# cSLIM-SA_power.net
KiCad netlist of a schematic drawn in Altium Designer
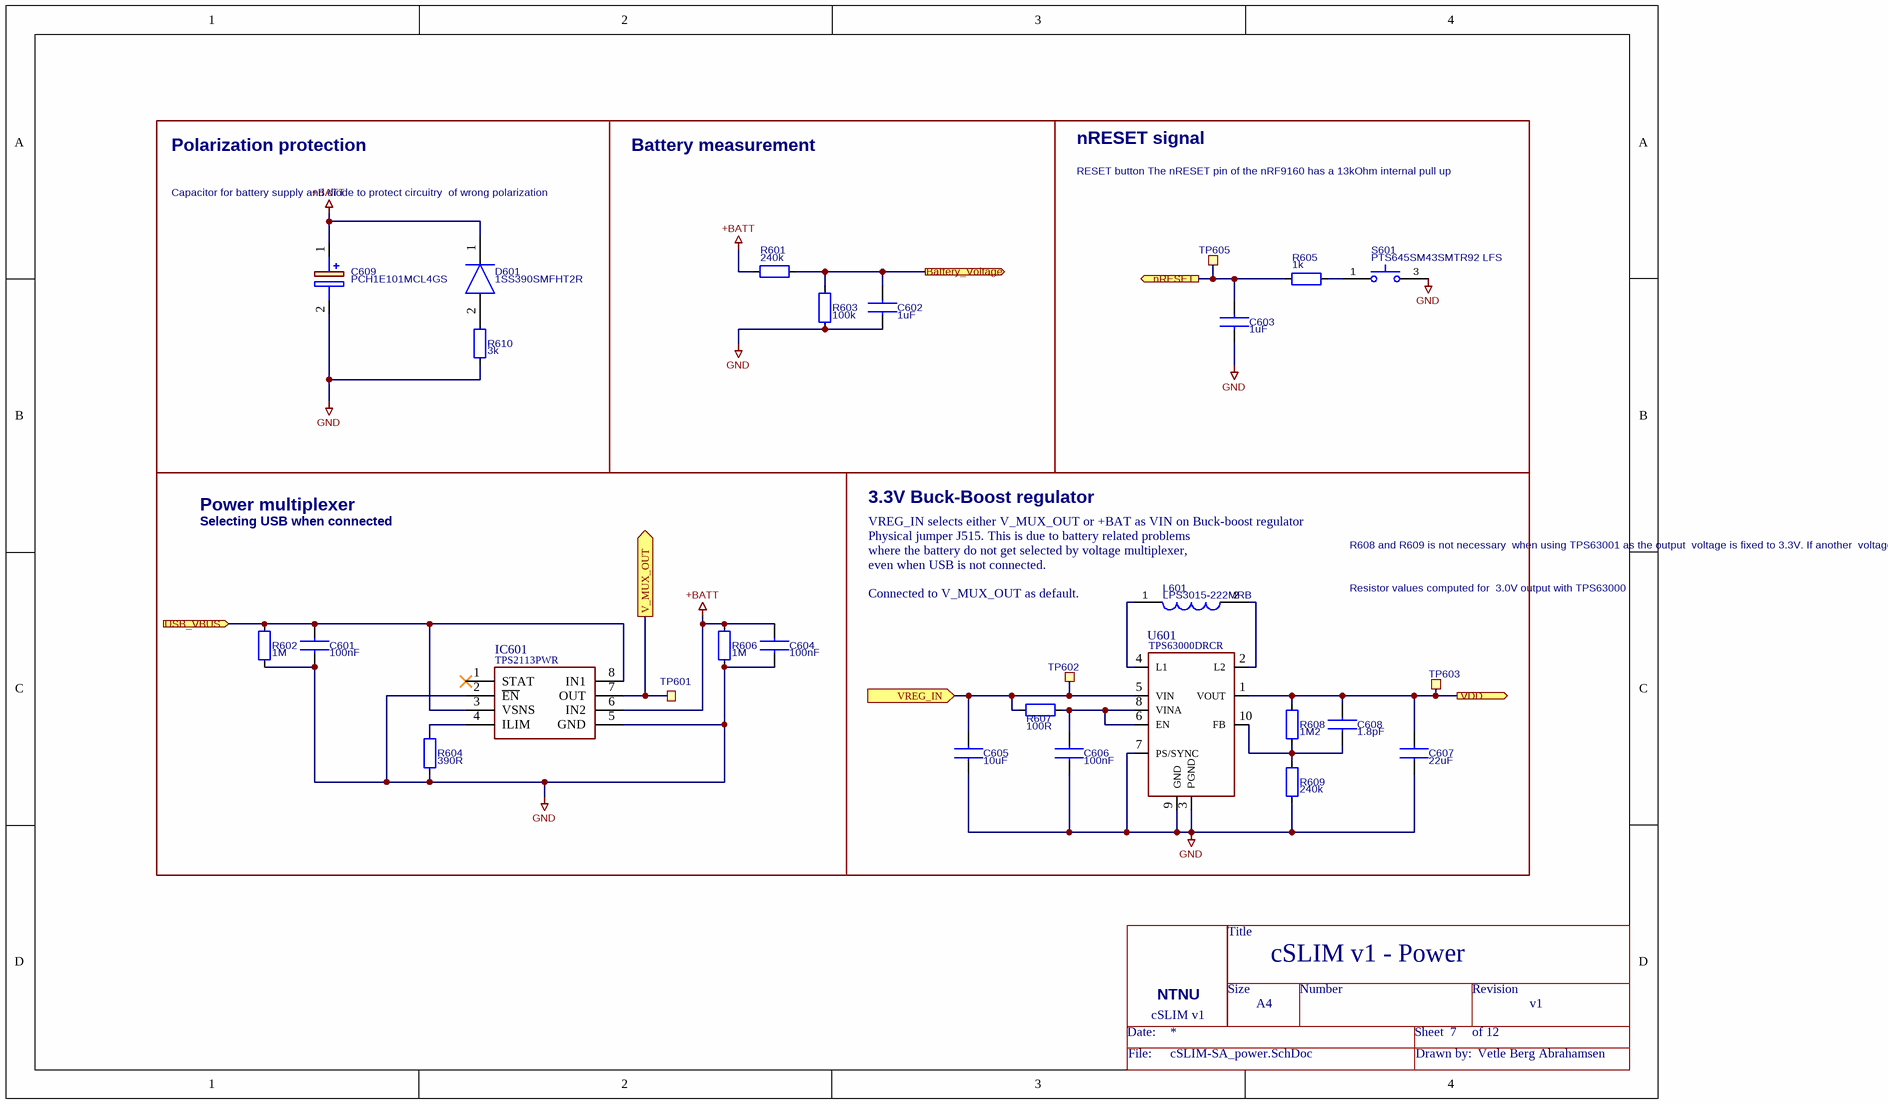
[diagram p0: cSLIM-SA_power.SchDoc]

(export (version "E")
  (design (tool "Eeschema 10.0.6"))
  (components
    (comp (ref "C601")
      (value "100nF")
      (footprint "cSLIM-SA:CAPC1608X90N")
      (description "Capacitor")
      (fields (field (name "MANUFACTURER_PART_NUMBER") "CL10B104KB8NNNL"))
      (libsource (lib "cSLIM-SA") (part "C"))
    )
    (comp (ref "C602")
      (value "1uF")
      (footprint "cSLIM-SA:CAPC1608X90N")
      (description "Capacitor")
      (fields (field (name "MANUFACTURER_PART_NUMBER") "CL10A105KO8NNNC"))
      (libsource (lib "cSLIM-SA") (part "C"))
    )
    (comp (ref "C603")
      (value "1uF")
      (footprint "cSLIM-SA:CAPC1608X90N")
      (description "Capacitor")
      (fields (field (name "MANUFACTURER_PART_NUMBER") "CL10A105KO8NNNC"))
      (libsource (lib "cSLIM-SA") (part "C"))
    )
    (comp (ref "C604")
      (value "100nF")
      (footprint "cSLIM-SA:CAPC1608X90N")
      (description "Capacitor")
      (fields (field (name "MANUFACTURER_PART_NUMBER") "CL10B104KB8NNNL"))
      (libsource (lib "cSLIM-SA") (part "C"))
    )
    (comp (ref "C605")
      (value "10uF")
      (footprint "cSLIM-SA:CAPC1608X90N")
      (description "Capacitor")
      (fields (field (name "MANUFACTURER_PART_NUMBER") "CL10X106MP8NRNC"))
      (libsource (lib "cSLIM-SA") (part "C"))
    )
    (comp (ref "C606")
      (value "100nF")
      (footprint "cSLIM-SA:CAPC1608X90N")
      (description "Capacitor")
      (fields (field (name "MANUFACTURER_PART_NUMBER") "CL10B104KB8NNNL"))
      (libsource (lib "cSLIM-SA") (part "C"))
    )
    (comp (ref "C607")
      (value "22uF")
      (footprint "cSLIM-SA:CAPC1608X90N")
      (description "Capacitor")
      (fields (field (name "MANUFACTURER_PART_NUMBER") "CL10A226KQ8NRNE"))
      (libsource (lib "cSLIM-SA") (part "C"))
    )
    (comp (ref "C608")
      (value "1.8pF")
      (footprint "cSLIM-SA:CAPC1608X90N")
      (description "Capacitor")
      (fields (field (name "MANUFACTURER_PART_NUMBER") "CL10C1R8BB8NNNC"))
      (libsource (lib "cSLIM-SA") (part "C"))
    )
    (comp (ref "C609")
      (value "PCH1E101MCL4GS")
      (footprint "cSLIM-SA:CAPAE660X840N")
      (description "Aluminium Organic Polymer Capacitors 100UF 25V ESR=27")
      (fields (field (name "MOUSER PART NUMBER") "647-PCH1E101MCL4GS"))
      (libsource (lib "cSLIM-SA") (part "PCH1E101MCL4GS"))
    )
    (comp (ref "D601")
      (value "1SS390SMFHT2R")
      (footprint "cSLIM-SA:SODFL1608X70N")
      (description "RF Diode PIN - Single 35V 100 mA EMD2")
      (fields (field (name "MOUSER PART NUMBER") "755-1SS390SMFHT2R"))
      (libsource (lib "cSLIM-SA") (part "1SS390SMFHT2R"))
    )
    (comp (ref "IC601")
      (value "TPS2113PWR")
      (footprint "cSLIM-SA:SOP65P640X120-8N")
      (description "OR Controller Source Selector Switch N-Channel 2:1 8-TSSOP")
      (fields (field (name "MOUSER PART NUMBER") "595-TPS2113PWR"))
      (libsource (lib "cSLIM-SA") (part "TPS2113PWR"))
    )
    (comp (ref "L601")
      (value "LPS3015-222MRB")
      (footprint "cSLIM-SA:LPS3015")
      (libsource (lib "cSLIM-SA") (part "LPS3015-103MRB"))
    )
    (comp (ref "R601")
      (value "240k")
      (footprint "cSLIM-SA:RESC1608X55N")
      (fields (field (name "MANUFACTURER_PART_NUMBER") "RC0603FR-07240KL"))
      (libsource (lib "cSLIM-SA") (part "R"))
    )
    (comp (ref "R602")
      (value "1M")
      (footprint "cSLIM-SA:RESC1608X55N")
      (fields (field (name "MANUFACTURER_PART_NUMBER") "RC0603FR-131ML"))
      (libsource (lib "") (part "R_1"))
    )
    (comp (ref "R603")
      (value "100k")
      (footprint "cSLIM-SA:RESC1608X55N")
      (fields (field (name "MANUFACTURER_PART_NUMBER") "RC0603FR-07100KL"))
      (libsource (lib "") (part "R_1"))
    )
    (comp (ref "R604")
      (value "390R")
      (footprint "cSLIM-SA:RESC1608X55N")
      (fields (field (name "MANUFACTURER_PART_NUMBER") "RC0603JR-07390RL"))
      (libsource (lib "") (part "R_1"))
    )
    (comp (ref "R605")
      (value "1k")
      (footprint "cSLIM-SA:RESC1608X55N")
      (fields (field (name "MANUFACTURER_PART_NUMBER") "RC0603FR-071KL"))
      (libsource (lib "") (part "R_2"))
    )
    (comp (ref "R606")
      (value "1M")
      (footprint "cSLIM-SA:RESC1608X55N")
      (fields (field (name "MANUFACTURER_PART_NUMBER") "RC0603FR-131ML"))
      (libsource (lib "") (part "R_1"))
    )
    (comp (ref "R607")
      (value "100R")
      (footprint "cSLIM-SA:RESC1608X55N")
      (fields (field (name "MANUFACTURER_PART_NUMBER") "RC0603FR-07100RL"))
      (libsource (lib "cSLIM-SA") (part "R"))
    )
    (comp (ref "R608")
      (value "1M2")
      (footprint "cSLIM-SA:RESC1608X55N")
      (fields (field (name "MANUFACTURER_PART_NUMBER") "RC0603FR-071M2L"))
      (libsource (lib "") (part "R_1"))
    )
    (comp (ref "R609")
      (value "240k")
      (footprint "cSLIM-SA:RESC1608X55N")
      (fields (field (name "MANUFACTURER_PART_NUMBER") "RC0603FR-07240KL"))
      (libsource (lib "") (part "R_1"))
    )
    (comp (ref "R610")
      (value "3k")
      (footprint "cSLIM-SA:RESC1608X55N")
      (fields (field (name "MANUFACTURER_PART_NUMBER") "RC0603FR-073KL"))
      (libsource (lib "") (part "R_1"))
    )
    (comp (ref "S601")
      (value "PTS645SM43SMTR92 LFS")
      (footprint "cSLIM-SA:PTS645(SMT)")
      (description "SWITCH TACTILE SPST-NO 0.05A 12V -  used 1-3 (2-4 not in use)")
      (fields
        (field (name "MOUSER PART NUMBER") "611-TLSA070JLFS")
        (field (name "MANUFACTURER_PART_NUMBER") "TLS A 070J LFS")
      )
      (libsource (lib "cSLIM-SA") (part "PTS645SM43SMTR92LFS"))
    )
    (comp (ref "TP601")
      (value "TP")
      (footprint "cSLIM-SA:TP_SMD_Ø1.0mm")
      (description "Test points")
      (libsource (lib "") (part "TP_1"))
    )
    (comp (ref "TP602")
      (value "TP")
      (footprint "cSLIM-SA:TP_SMD_Ø1.0mm")
      (description "Test points")
      (libsource (lib "cSLIM-SA") (part "TP"))
    )
    (comp (ref "TP603")
      (value "TP")
      (footprint "cSLIM-SA:TP_SMD_Ø1.0mm")
      (description "Test points")
      (libsource (lib "cSLIM-SA") (part "TP"))
    )
    (comp (ref "TP605")
      (value "TP")
      (footprint "cSLIM-SA:TP_SMD_Ø1.0mm")
      (description "Test points")
      (libsource (lib "cSLIM-SA") (part "TP"))
    )
    (comp (ref "U601")
      (value "TPS63000DRCR")
      (footprint "cSLIM-SA:TPS63002DRCR")
      (fields (field (name "MOUSER PART NUMBER") "595-TPS63000DRCR"))
      (libsource (lib "cSLIM-SA") (part "TPS63000DRCR"))
    )
  )
  (nets
    (net (code "1") (name "+BATT") (class "Default")
      (node (ref "C604") (pin "1") (pinfunction "1_1") (pintype "passive"))
      (node (ref "C609") (pin "1") (pinfunction "+_1") (pintype "passive"))
      (node (ref "D601") (pin "1") (pinfunction "K_1") (pintype "passive"))
      (node (ref "IC601") (pin "6") (pinfunction "IN2_6") (pintype "passive"))
      (node (ref "R601") (pin "2") (pinfunction "2_2") (pintype "passive"))
      (node (ref "R606") (pin "1") (pinfunction "1_1") (pintype "passive"))
    )
    (net (code "2") (name "/Battery_Voltage") (class "Default")
      (node (ref "C602") (pin "1") (pinfunction "1_1") (pintype "passive"))
      (node (ref "R601") (pin "1") (pinfunction "1_1") (pintype "passive"))
      (node (ref "R603") (pin "1") (pinfunction "1_1") (pintype "passive"))
    )
    (net (code "3") (name "/USB_VBUS") (class "Default")
      (node (ref "C601") (pin "1") (pinfunction "1_1") (pintype "passive"))
      (node (ref "IC601") (pin "3") (pinfunction "VSNS_3") (pintype "passive"))
      (node (ref "IC601") (pin "8") (pinfunction "IN1_8") (pintype "passive"))
      (node (ref "R602") (pin "1") (pinfunction "1_1") (pintype "passive"))
    )
    (net (code "4") (name "/VDD") (class "Default")
      (node (ref "C607") (pin "1") (pinfunction "1_1") (pintype "passive"))
      (node (ref "C608") (pin "1") (pinfunction "1_1") (pintype "passive"))
      (node (ref "R608") (pin "1") (pinfunction "1_1") (pintype "passive"))
      (node (ref "TP603") (pin "1") (pinfunction "1_1") (pintype "passive"))
      (node (ref "U601") (pin "1") (pinfunction "VOUT_1") (pintype "passive"))
    )
    (net (code "5") (name "/VREG_IN") (class "Default")
      (node (ref "C605") (pin "1") (pinfunction "1_1") (pintype "passive"))
      (node (ref "R607") (pin "2") (pinfunction "2_2") (pintype "passive"))
      (node (ref "TP602") (pin "1") (pinfunction "1_1") (pintype "passive"))
      (node (ref "U601") (pin "5") (pinfunction "VIN_5") (pintype "passive"))
    )
    (net (code "6") (name "/V_MUX_OUT") (class "Default")
      (node (ref "IC601") (pin "7") (pinfunction "OUT_7") (pintype "passive"))
      (node (ref "TP601") (pin "1") (pinfunction "1_1") (pintype "passive"))
    )
    (net (code "7") (name "/nRESET") (class "Default")
      (node (ref "C603") (pin "1") (pinfunction "1_1") (pintype "passive"))
      (node (ref "R605") (pin "1") (pinfunction "1_1") (pintype "passive"))
      (node (ref "TP605") (pin "1") (pinfunction "1_1") (pintype "passive"))
    )
    (net (code "8") (name "GND") (class "Default")
      (node (ref "C601") (pin "2") (pinfunction "2_2") (pintype "passive"))
      (node (ref "C602") (pin "2") (pinfunction "2_2") (pintype "passive"))
      (node (ref "C603") (pin "2") (pinfunction "2_2") (pintype "passive"))
      (node (ref "C604") (pin "2") (pinfunction "2_2") (pintype "passive"))
      (node (ref "C605") (pin "2") (pinfunction "2_2") (pintype "passive"))
      (node (ref "C606") (pin "2") (pinfunction "2_2") (pintype "passive"))
      (node (ref "C607") (pin "2") (pinfunction "2_2") (pintype "passive"))
      (node (ref "C609") (pin "2") (pinfunction "-_2") (pintype "passive"))
      (node (ref "IC601") (pin "2") (pinfunction "~{EN}_2") (pintype "passive"))
      (node (ref "IC601") (pin "5") (pinfunction "GND_5") (pintype "passive"))
      (node (ref "R602") (pin "2") (pinfunction "2_2") (pintype "passive"))
      (node (ref "R603") (pin "2") (pinfunction "2_2") (pintype "passive"))
      (node (ref "R604") (pin "2") (pinfunction "2_2") (pintype "passive"))
      (node (ref "R606") (pin "2") (pinfunction "2_2") (pintype "passive"))
      (node (ref "R609") (pin "2") (pinfunction "2_2") (pintype "passive"))
      (node (ref "R610") (pin "2") (pinfunction "2_2") (pintype "passive"))
      (node (ref "S601") (pin "3") (pinfunction "3_3") (pintype "passive"))
      (node (ref "U601") (pin "3") (pinfunction "PGND_3") (pintype "passive"))
      (node (ref "U601") (pin "7") (pinfunction "PS/SYNC_7") (pintype "passive"))
      (node (ref "U601") (pin "9") (pinfunction "GND_9") (pintype "passive"))
    )
    (net (code "9") (name "Net-(D601-A)") (class "Default")
      (node (ref "D601") (pin "2") (pinfunction "A_2") (pintype "passive"))
      (node (ref "R610") (pin "1") (pinfunction "1_1") (pintype "passive"))
    )
    (net (code "10") (name "Net-(IC601-ILIM)") (class "Default")
      (node (ref "IC601") (pin "4") (pinfunction "ILIM_4") (pintype "passive"))
      (node (ref "R604") (pin "1") (pinfunction "1_1") (pintype "passive"))
    )
    (net (code "11") (name "Net-(R605-Pad2)") (class "Default")
      (node (ref "R605") (pin "2") (pinfunction "2_2") (pintype "passive"))
      (node (ref "S601") (pin "1") (pinfunction "1_1") (pintype "passive"))
    )
    (net (code "12") (name "Net-(U601-EN)") (class "Default")
      (node (ref "C606") (pin "1") (pinfunction "1_1") (pintype "passive"))
      (node (ref "R607") (pin "1") (pinfunction "1_1") (pintype "passive"))
      (node (ref "U601") (pin "6") (pinfunction "EN_6") (pintype "passive"))
      (node (ref "U601") (pin "8") (pinfunction "VINA_8") (pintype "passive"))
    )
    (net (code "13") (name "Net-(U601-FB)") (class "Default")
      (node (ref "C608") (pin "2") (pinfunction "2_2") (pintype "passive"))
      (node (ref "R608") (pin "2") (pinfunction "2_2") (pintype "passive"))
      (node (ref "R609") (pin "1") (pinfunction "1_1") (pintype "passive"))
      (node (ref "U601") (pin "10") (pinfunction "FB_10") (pintype "passive"))
    )
    (net (code "14") (name "Net-(U601-L1)") (class "Default")
      (node (ref "L601") (pin "1") (pinfunction "1_1") (pintype "passive"))
      (node (ref "U601") (pin "4") (pinfunction "L1_4") (pintype "passive"))
    )
    (net (code "15") (name "Net-(U601-L2)") (class "Default")
      (node (ref "L601") (pin "2") (pinfunction "2_2") (pintype "passive"))
      (node (ref "U601") (pin "2") (pinfunction "L2_2") (pintype "passive"))
    )
    (net (code "16") (name "unconnected-(IC601-STAT-Pad1)") (class "Default")
      (node (ref "IC601") (pin "1") (pinfunction "STAT_1") (pintype "passive+no_connect"))
    )
  )
)
